# HeartSound_LungSound.net
KiCad netlist of a schematic drawn in Altium Designer
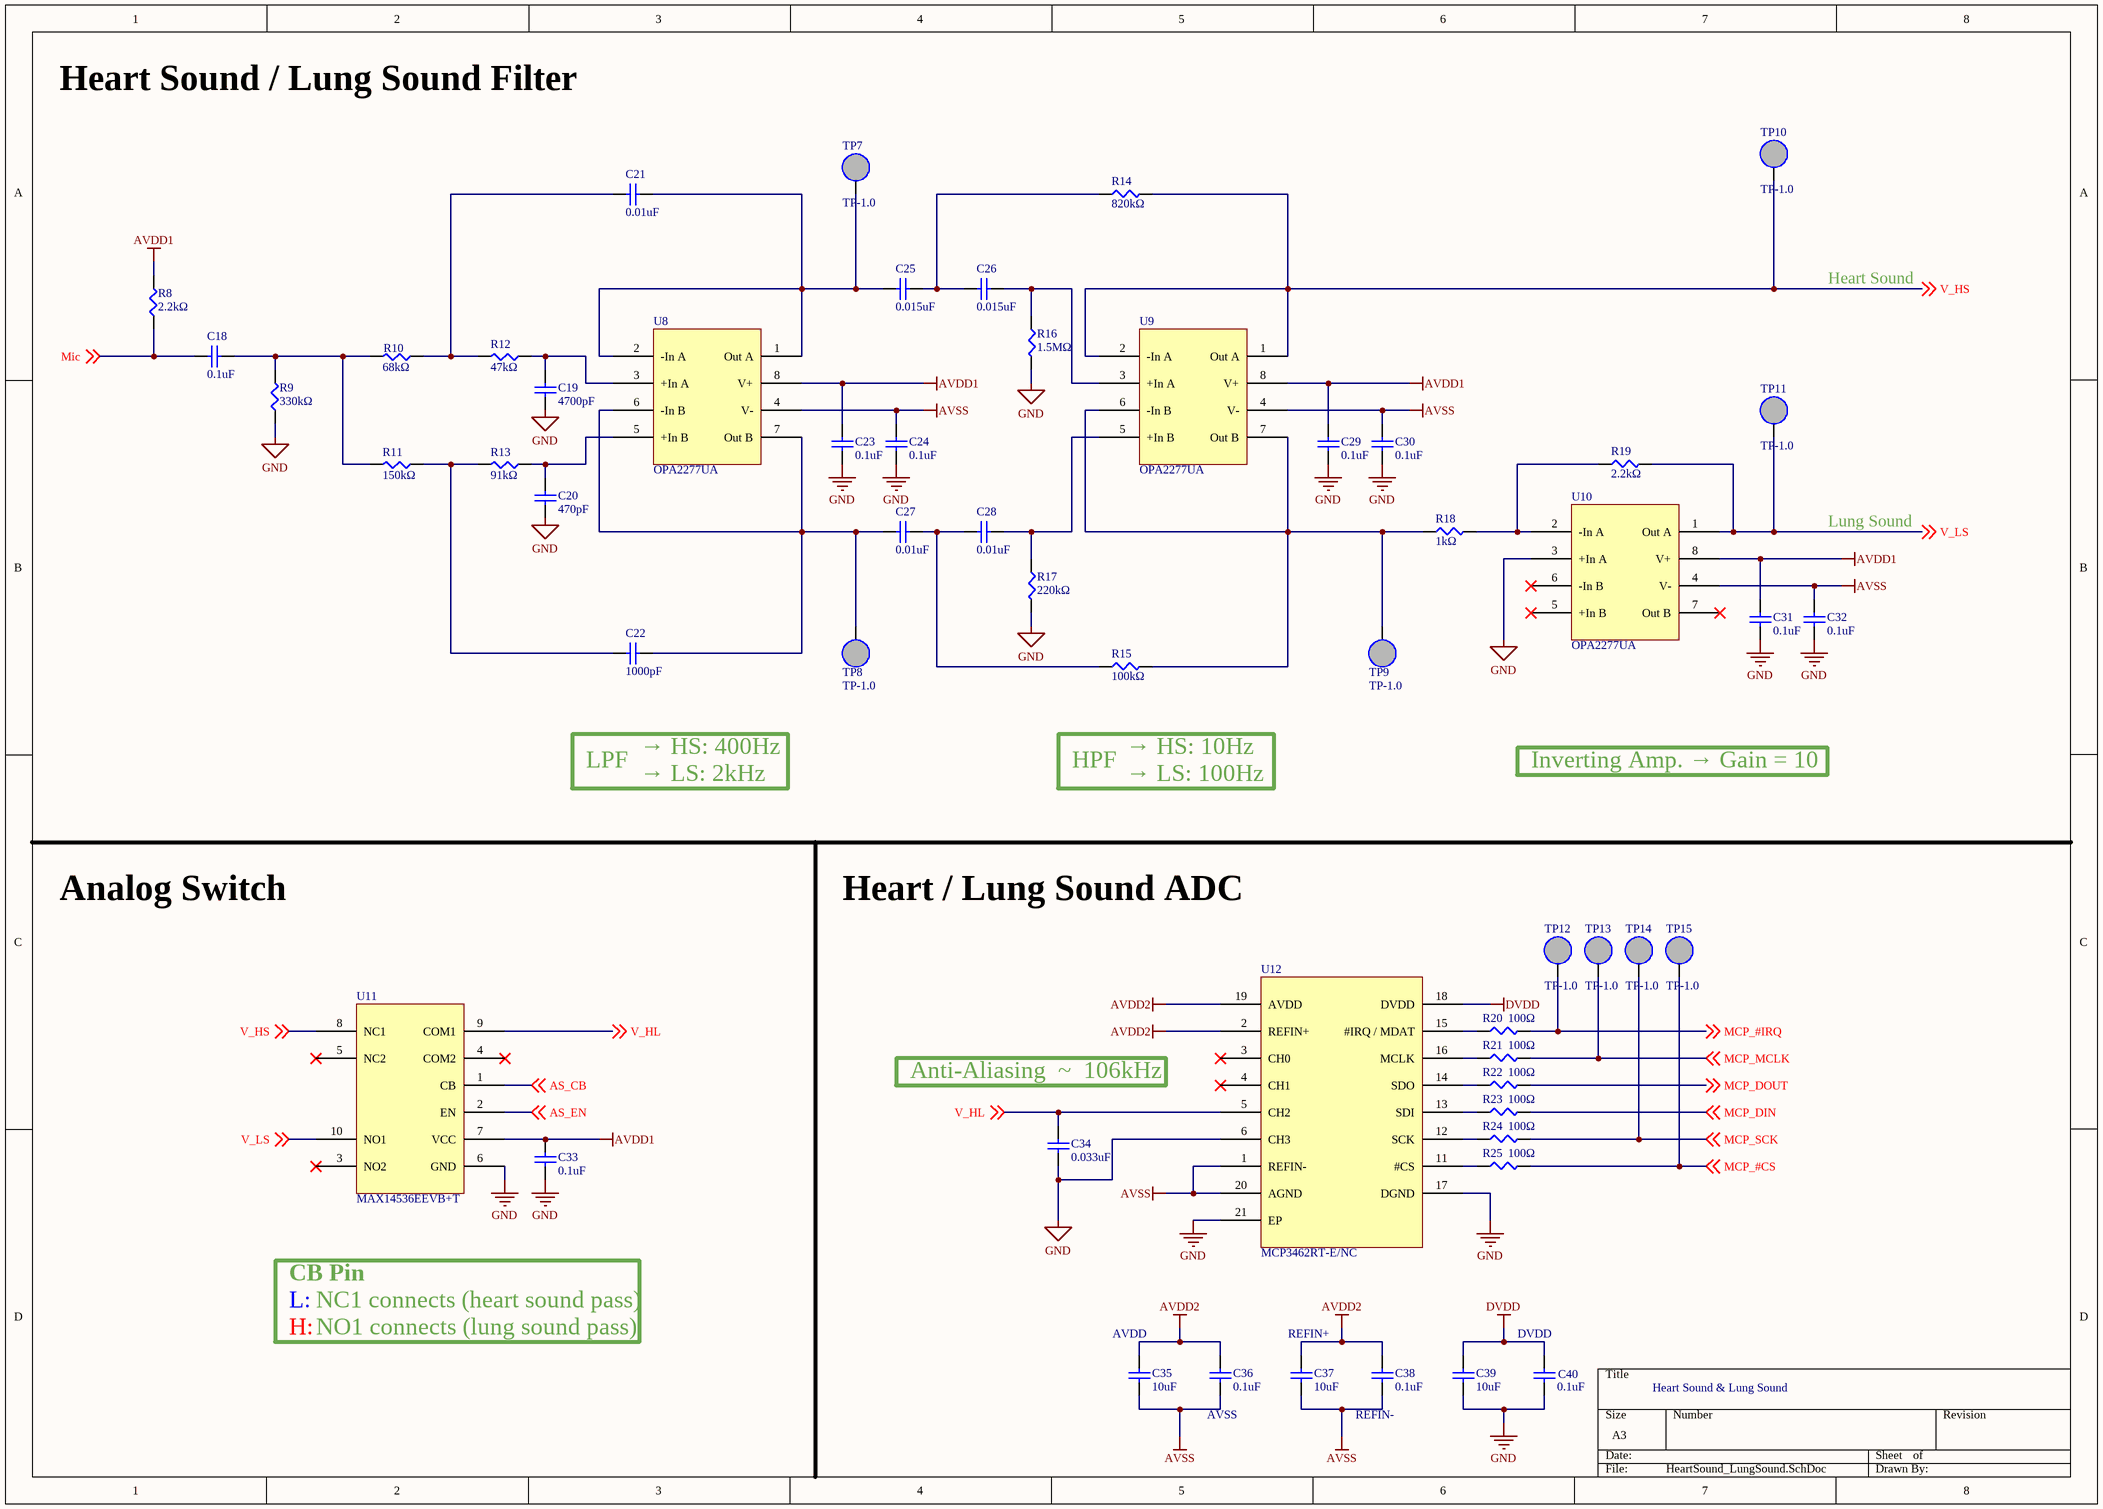
[diagram p0: HeartSound_LungSound.SchDoc]

(export (version "E")
  (design (tool "Eeschema 10.0.6"))
  (components
    (comp (ref "C18")
      (value "0.1uF")
      (footprint "0402")
      (description "MLCC-0402")
      (libsource (lib "MLCC") (part "0402"))
    )
    (comp (ref "C19")
      (value "4700pF")
      (footprint "0402")
      (description "MLCC-0402")
      (libsource (lib "MLCC") (part "0402"))
    )
    (comp (ref "C20")
      (value "470pF")
      (footprint "0402")
      (description "MLCC-0402")
      (libsource (lib "MLCC") (part "0402"))
    )
    (comp (ref "C21")
      (value "0.01uF")
      (footprint "0402")
      (description "MLCC-0402")
      (libsource (lib "MLCC") (part "0402"))
    )
    (comp (ref "C22")
      (value "1000pF")
      (footprint "0402")
      (description "MLCC-0402")
      (libsource (lib "MLCC") (part "0402"))
    )
    (comp (ref "C23")
      (value "0.1uF")
      (footprint "0402")
      (description "MLCC-0402")
      (libsource (lib "MLCC") (part "0402"))
    )
    (comp (ref "C24")
      (value "0.1uF")
      (footprint "0402")
      (description "MLCC-0402")
      (libsource (lib "MLCC") (part "0402"))
    )
    (comp (ref "C25")
      (value "0.015uF")
      (footprint "0402")
      (description "MLCC-0402")
      (libsource (lib "MLCC") (part "0402"))
    )
    (comp (ref "C26")
      (value "0.015uF")
      (footprint "0402")
      (description "MLCC-0402")
      (libsource (lib "MLCC") (part "0402"))
    )
    (comp (ref "C27")
      (value "0.01uF")
      (footprint "0402")
      (description "MLCC-0402")
      (libsource (lib "MLCC") (part "0402"))
    )
    (comp (ref "C28")
      (value "0.01uF")
      (footprint "0402")
      (description "MLCC-0402")
      (libsource (lib "MLCC") (part "0402"))
    )
    (comp (ref "C29")
      (value "0.1uF")
      (footprint "0402")
      (description "MLCC-0402")
      (libsource (lib "MLCC") (part "0402"))
    )
    (comp (ref "C30")
      (value "0.1uF")
      (footprint "0402")
      (description "MLCC-0402")
      (libsource (lib "MLCC") (part "0402"))
    )
    (comp (ref "C31")
      (value "0.1uF")
      (footprint "0402")
      (description "MLCC-0402")
      (libsource (lib "MLCC") (part "0402"))
    )
    (comp (ref "C32")
      (value "0.1uF")
      (footprint "0402")
      (description "MLCC-0402")
      (libsource (lib "MLCC") (part "0402"))
    )
    (comp (ref "C33")
      (value "0.1uF")
      (footprint "0402")
      (description "MLCC-0402")
      (libsource (lib "MLCC") (part "0402"))
    )
    (comp (ref "C34")
      (value "0.033uF")
      (footprint "0402")
      (description "MLCC-0402")
      (libsource (lib "MLCC") (part "0402"))
    )
    (comp (ref "C35")
      (value "10uF")
      (footprint "0603")
      (description "MLCC-0603")
      (libsource (lib "MLCC") (part "0603"))
    )
    (comp (ref "C36")
      (value "0.1uF")
      (footprint "0402")
      (description "MLCC-0402")
      (libsource (lib "MLCC") (part "0402"))
    )
    (comp (ref "C37")
      (value "10uF")
      (footprint "0603")
      (description "MLCC-0603")
      (libsource (lib "MLCC") (part "0603"))
    )
    (comp (ref "C38")
      (value "0.1uF")
      (footprint "0402")
      (description "MLCC-0402")
      (libsource (lib "MLCC") (part "0402"))
    )
    (comp (ref "C39")
      (value "10uF")
      (footprint "0603")
      (description "MLCC-0603")
      (libsource (lib "MLCC") (part "0603"))
    )
    (comp (ref "C40")
      (value "0.1uF")
      (footprint "0402")
      (description "MLCC-0402")
      (libsource (lib "MLCC") (part "0402"))
    )
    (comp (ref "R8")
      (value "2.2kΩ")
      (footprint "0402")
      (description "Resistor_SMD_0402")
      (fields (field (name "AUTHORBY") "yjlab"))
      (libsource (lib "Resistor") (part "0402"))
    )
    (comp (ref "R9")
      (value "330kΩ")
      (footprint "0402")
      (description "Resistor_SMD_0402")
      (fields (field (name "AUTHORBY") "yjlab"))
      (libsource (lib "Resistor") (part "0402"))
    )
    (comp (ref "R10")
      (value "68kΩ")
      (footprint "0402")
      (description "Resistor_SMD_0402")
      (fields (field (name "AUTHORBY") "yjlab"))
      (libsource (lib "Resistor") (part "0402"))
    )
    (comp (ref "R11")
      (value "150kΩ")
      (footprint "0402")
      (description "Resistor_SMD_0402")
      (fields (field (name "AUTHORBY") "yjlab"))
      (libsource (lib "Resistor") (part "0402"))
    )
    (comp (ref "R12")
      (value "47kΩ")
      (footprint "0402")
      (description "Resistor_SMD_0402")
      (fields (field (name "AUTHORBY") "yjlab"))
      (libsource (lib "Resistor") (part "0402"))
    )
    (comp (ref "R13")
      (value "91kΩ")
      (footprint "0402")
      (description "Resistor_SMD_0402")
      (fields (field (name "AUTHORBY") "yjlab"))
      (libsource (lib "Resistor") (part "0402"))
    )
    (comp (ref "R14")
      (value "820kΩ")
      (footprint "0402")
      (description "Resistor_SMD_0402")
      (fields (field (name "AUTHORBY") "yjlab"))
      (libsource (lib "Resistor") (part "0402"))
    )
    (comp (ref "R15")
      (value "100kΩ")
      (footprint "0402")
      (description "Resistor_SMD_0402")
      (fields (field (name "AUTHORBY") "yjlab"))
      (libsource (lib "Resistor") (part "0402"))
    )
    (comp (ref "R16")
      (value "1.5MΩ")
      (footprint "0402")
      (description "Resistor_SMD_0402")
      (fields (field (name "AUTHORBY") "yjlab"))
      (libsource (lib "Resistor") (part "0402"))
    )
    (comp (ref "R17")
      (value "220kΩ")
      (footprint "0402")
      (description "Resistor_SMD_0402")
      (fields (field (name "AUTHORBY") "yjlab"))
      (libsource (lib "Resistor") (part "0402"))
    )
    (comp (ref "R18")
      (value "1kΩ")
      (footprint "0402")
      (description "Resistor_SMD_0402")
      (fields (field (name "AUTHORBY") "yjlab"))
      (libsource (lib "Resistor") (part "0402"))
    )
    (comp (ref "R19")
      (value "2.2kΩ")
      (footprint "0402")
      (description "Resistor_SMD_0402")
      (fields (field (name "AUTHORBY") "yjlab"))
      (libsource (lib "Resistor") (part "0402"))
    )
    (comp (ref "R20")
      (value "100Ω")
      (footprint "0402")
      (description "Resistor_SMD_0402")
      (fields (field (name "AUTHORBY") "yjlab"))
      (libsource (lib "Resistor") (part "0402"))
    )
    (comp (ref "R21")
      (value "100Ω")
      (footprint "0402")
      (description "Resistor_SMD_0402")
      (fields (field (name "AUTHORBY") "yjlab"))
      (libsource (lib "Resistor") (part "0402"))
    )
    (comp (ref "R22")
      (value "100Ω")
      (footprint "0402")
      (description "Resistor_SMD_0402")
      (fields (field (name "AUTHORBY") "yjlab"))
      (libsource (lib "Resistor") (part "0402"))
    )
    (comp (ref "R23")
      (value "100Ω")
      (footprint "0402")
      (description "Resistor_SMD_0402")
      (fields (field (name "AUTHORBY") "yjlab"))
      (libsource (lib "Resistor") (part "0402"))
    )
    (comp (ref "R24")
      (value "100Ω")
      (footprint "0402")
      (description "Resistor_SMD_0402")
      (fields (field (name "AUTHORBY") "yjlab"))
      (libsource (lib "Resistor") (part "0402"))
    )
    (comp (ref "R25")
      (value "100Ω")
      (footprint "0402")
      (description "Resistor_SMD_0402")
      (fields (field (name "AUTHORBY") "yjlab"))
      (libsource (lib "Resistor") (part "0402"))
    )
    (comp (ref "TP7")
      (value "TP-1.0")
      (footprint "Testpoint")
      (libsource (lib "Testpoint") (part "Testpoint"))
    )
    (comp (ref "TP8")
      (value "TP-1.0")
      (footprint "Testpoint")
      (libsource (lib "Testpoint") (part "Testpoint"))
    )
    (comp (ref "TP9")
      (value "TP-1.0")
      (footprint "Testpoint")
      (libsource (lib "Testpoint") (part "Testpoint"))
    )
    (comp (ref "TP10")
      (value "TP-1.0")
      (footprint "Testpoint")
      (libsource (lib "Testpoint") (part "Testpoint"))
    )
    (comp (ref "TP11")
      (value "TP-1.0")
      (footprint "Testpoint")
      (libsource (lib "Testpoint") (part "Testpoint"))
    )
    (comp (ref "TP12")
      (value "TP-1.0")
      (footprint "Testpoint")
      (libsource (lib "Testpoint") (part "Testpoint"))
    )
    (comp (ref "TP13")
      (value "TP-1.0")
      (footprint "Testpoint")
      (libsource (lib "Testpoint") (part "Testpoint"))
    )
    (comp (ref "TP14")
      (value "TP-1.0")
      (footprint "Testpoint")
      (libsource (lib "Testpoint") (part "Testpoint"))
    )
    (comp (ref "TP15")
      (value "TP-1.0")
      (footprint "Testpoint")
      (libsource (lib "Testpoint") (part "Testpoint"))
    )
    (comp (ref "U8")
      (value "OPA2277UA")
      (footprint "SOIC-8")
      (description "High Precision OP Amp, 2 Channel")
      (libsource (lib "OPAx277") (part "OPA2277UA"))
    )
    (comp (ref "U9")
      (value "OPA2277UA")
      (footprint "SOIC-8")
      (description "High Precision OP Amp, 2 Channel")
      (libsource (lib "OPAx277") (part "OPA2277UA"))
    )
    (comp (ref "U10")
      (value "OPA2277UA")
      (footprint "SOIC-8")
      (description "High Precision OP Amp, 2 Channel")
      (libsource (lib "OPAx277") (part "OPA2277UA"))
    )
    (comp (ref "U11")
      (value "MAX14536EEVB+T")
      (footprint "ULTRA-TQFN-10")
      (description "Analog Switch, 0.135 (Ω) On-Resistence")
      (libsource (lib "MAX14536E") (part "MAX14536EEVB+T"))
    )
    (comp (ref "U12")
      (value "MCP3462RT-E/NC")
      (footprint "UQFN-20")
      (description "Delta-to-Sigma ADC, 16 Bit, 2 Channel")
      (libsource (lib "MCP346x") (part "MCP3462RT-E/NC"))
    )
  )
  (nets
    (net (code "1") (name "AS_CB") (class "Default")
      (node (ref "U11") (pin "1") (pinfunction "CB_1") (pintype "passive"))
    )
    (net (code "2") (name "AS_EN") (class "Default")
      (node (ref "U11") (pin "2") (pinfunction "EN_2") (pintype "passive"))
    )
    (net (code "3") (name "AVDD1") (class "Default")
      (node (ref "C23") (pin "1") (pinfunction "1_1") (pintype "passive"))
      (node (ref "C29") (pin "2") (pinfunction "2_2") (pintype "passive"))
      (node (ref "C31") (pin "2") (pinfunction "2_2") (pintype "passive"))
      (node (ref "C33") (pin "2") (pinfunction "2_2") (pintype "passive"))
      (node (ref "R8") (pin "2") (pinfunction "2_2") (pintype "passive"))
      (node (ref "U10") (pin "8") (pinfunction "V+_8") (pintype "passive"))
      (node (ref "U11") (pin "7") (pinfunction "VCC_7") (pintype "passive"))
      (node (ref "U8") (pin "8") (pinfunction "V+_8") (pintype "passive"))
      (node (ref "U9") (pin "8") (pinfunction "V+_8") (pintype "passive"))
    )
    (net (code "4") (name "AVDD2") (class "Default")
      (node (ref "C35") (pin "2") (pinfunction "2_2") (pintype "passive"))
      (node (ref "C36") (pin "2") (pinfunction "2_2") (pintype "passive"))
      (node (ref "C37") (pin "1") (pinfunction "1_1") (pintype "passive"))
      (node (ref "C38") (pin "2") (pinfunction "2_2") (pintype "passive"))
      (node (ref "U12") (pin "19") (pinfunction "AVDD_19") (pintype "passive"))
      (node (ref "U12") (pin "2") (pinfunction "REFIN+_2") (pintype "passive"))
    )
    (net (code "5") (name "AVSS") (class "Default")
      (node (ref "C24") (pin "2") (pinfunction "2_2") (pintype "passive"))
      (node (ref "C30") (pin "1") (pinfunction "1_1") (pintype "passive"))
      (node (ref "C32") (pin "1") (pinfunction "1_1") (pintype "passive"))
      (node (ref "C35") (pin "1") (pinfunction "1_1") (pintype "passive"))
      (node (ref "C36") (pin "1") (pinfunction "1_1") (pintype "passive"))
      (node (ref "C37") (pin "2") (pinfunction "2_2") (pintype "passive"))
      (node (ref "C38") (pin "1") (pinfunction "1_1") (pintype "passive"))
      (node (ref "U10") (pin "4") (pinfunction "V-_4") (pintype "passive"))
      (node (ref "U12") (pin "1") (pinfunction "REFIN-_1") (pintype "passive"))
      (node (ref "U12") (pin "20") (pinfunction "AGND_20") (pintype "passive"))
      (node (ref "U8") (pin "4") (pinfunction "V-_4") (pintype "passive"))
      (node (ref "U9") (pin "4") (pinfunction "V-_4") (pintype "passive"))
    )
    (net (code "6") (name "DVDD") (class "Default")
      (node (ref "C39") (pin "2") (pinfunction "2_2") (pintype "passive"))
      (node (ref "C40") (pin "2") (pinfunction "2_2") (pintype "passive"))
      (node (ref "U12") (pin "18") (pinfunction "DVDD_18") (pintype "passive"))
    )
    (net (code "7") (name "GND") (class "Default")
      (node (ref "C19") (pin "2") (pinfunction "2_2") (pintype "passive"))
      (node (ref "C20") (pin "2") (pinfunction "2_2") (pintype "passive"))
      (node (ref "C23") (pin "2") (pinfunction "2_2") (pintype "passive"))
      (node (ref "C24") (pin "1") (pinfunction "1_1") (pintype "passive"))
      (node (ref "C29") (pin "1") (pinfunction "1_1") (pintype "passive"))
      (node (ref "C30") (pin "2") (pinfunction "2_2") (pintype "passive"))
      (node (ref "C31") (pin "1") (pinfunction "1_1") (pintype "passive"))
      (node (ref "C32") (pin "2") (pinfunction "2_2") (pintype "passive"))
      (node (ref "C33") (pin "1") (pinfunction "1_1") (pintype "passive"))
      (node (ref "C34") (pin "2") (pinfunction "2_2") (pintype "passive"))
      (node (ref "C39") (pin "1") (pinfunction "1_1") (pintype "passive"))
      (node (ref "C40") (pin "1") (pinfunction "1_1") (pintype "passive"))
      (node (ref "R16") (pin "2") (pinfunction "2_2") (pintype "passive"))
      (node (ref "R17") (pin "2") (pinfunction "2_2") (pintype "passive"))
      (node (ref "R9") (pin "1") (pinfunction "1_1") (pintype "passive"))
      (node (ref "U10") (pin "3") (pinfunction "+In_A_3") (pintype "passive"))
      (node (ref "U11") (pin "6") (pinfunction "GND_6") (pintype "passive"))
      (node (ref "U12") (pin "17") (pinfunction "DGND_17") (pintype "passive"))
      (node (ref "U12") (pin "21") (pinfunction "EP_21") (pintype "passive"))
      (node (ref "U12") (pin "6") (pinfunction "CH3_6") (pintype "passive"))
    )
    (net (code "8") (name "MCP_#CS") (class "Default")
      (node (ref "R25") (pin "2") (pinfunction "2_2") (pintype "passive"))
      (node (ref "TP15") (pin "1") (pinfunction "1_1") (pintype "passive"))
    )
    (net (code "9") (name "MCP_#IRQ") (class "Default")
      (node (ref "R20") (pin "2") (pinfunction "2_2") (pintype "passive"))
      (node (ref "TP12") (pin "1") (pinfunction "1_1") (pintype "passive"))
    )
    (net (code "10") (name "MCP_DIN") (class "Default")
      (node (ref "R23") (pin "2") (pinfunction "2_2") (pintype "passive"))
    )
    (net (code "11") (name "MCP_DOUT") (class "Default")
      (node (ref "R22") (pin "2") (pinfunction "2_2") (pintype "passive"))
    )
    (net (code "12") (name "MCP_MCLK") (class "Default")
      (node (ref "R21") (pin "2") (pinfunction "2_2") (pintype "passive"))
      (node (ref "TP13") (pin "1") (pinfunction "1_1") (pintype "passive"))
    )
    (net (code "13") (name "MCP_SCK") (class "Default")
      (node (ref "R24") (pin "2") (pinfunction "2_2") (pintype "passive"))
      (node (ref "TP14") (pin "1") (pinfunction "1_1") (pintype "passive"))
    )
    (net (code "14") (name "Mic") (class "Default")
      (node (ref "C18") (pin "1") (pinfunction "1_1") (pintype "passive"))
      (node (ref "R8") (pin "1") (pinfunction "1_1") (pintype "passive"))
    )
    (net (code "15") (name "Net-(C18-Pad2)") (class "Default")
      (node (ref "C18") (pin "2") (pinfunction "2_2") (pintype "passive"))
      (node (ref "R10") (pin "2") (pinfunction "2_2") (pintype "passive"))
      (node (ref "R11") (pin "2") (pinfunction "2_2") (pintype "passive"))
      (node (ref "R9") (pin "2") (pinfunction "2_2") (pintype "passive"))
    )
    (net (code "16") (name "Net-(C21-Pad2)") (class "Default")
      (node (ref "C21") (pin "2") (pinfunction "2_2") (pintype "passive"))
      (node (ref "R10") (pin "1") (pinfunction "1_1") (pintype "passive"))
      (node (ref "R12") (pin "2") (pinfunction "2_2") (pintype "passive"))
    )
    (net (code "17") (name "Net-(C22-Pad1)") (class "Default")
      (node (ref "C22") (pin "1") (pinfunction "1_1") (pintype "passive"))
      (node (ref "R11") (pin "1") (pinfunction "1_1") (pintype "passive"))
      (node (ref "R13") (pin "2") (pinfunction "2_2") (pintype "passive"))
    )
    (net (code "18") (name "Net-(C25-Pad1)") (class "Default")
      (node (ref "C25") (pin "1") (pinfunction "1_1") (pintype "passive"))
      (node (ref "C26") (pin "2") (pinfunction "2_2") (pintype "passive"))
      (node (ref "R14") (pin "1") (pinfunction "1_1") (pintype "passive"))
    )
    (net (code "19") (name "Net-(C27-Pad1)") (class "Default")
      (node (ref "C27") (pin "1") (pinfunction "1_1") (pintype "passive"))
      (node (ref "C28") (pin "2") (pinfunction "2_2") (pintype "passive"))
      (node (ref "R15") (pin "1") (pinfunction "1_1") (pintype "passive"))
    )
    (net (code "20") (name "Net-(U8-+In_A)") (class "Default")
      (node (ref "C19") (pin "1") (pinfunction "1_1") (pintype "passive"))
      (node (ref "R12") (pin "1") (pinfunction "1_1") (pintype "passive"))
      (node (ref "U8") (pin "3") (pinfunction "+In_A_3") (pintype "passive"))
    )
    (net (code "21") (name "Net-(U8-+In_B)") (class "Default")
      (node (ref "C20") (pin "1") (pinfunction "1_1") (pintype "passive"))
      (node (ref "R13") (pin "1") (pinfunction "1_1") (pintype "passive"))
      (node (ref "U8") (pin "5") (pinfunction "+In_B_5") (pintype "passive"))
    )
    (net (code "22") (name "Net-(U8--In_A)") (class "Default")
      (node (ref "C21") (pin "1") (pinfunction "1_1") (pintype "passive"))
      (node (ref "C25") (pin "2") (pinfunction "2_2") (pintype "passive"))
      (node (ref "TP7") (pin "1") (pinfunction "1_1") (pintype "passive"))
      (node (ref "U8") (pin "1") (pinfunction "Out_A_1") (pintype "passive"))
      (node (ref "U8") (pin "2") (pinfunction "-In_A_2") (pintype "passive"))
    )
    (net (code "23") (name "Net-(U8--In_B)") (class "Default")
      (node (ref "C22") (pin "2") (pinfunction "2_2") (pintype "passive"))
      (node (ref "C27") (pin "2") (pinfunction "2_2") (pintype "passive"))
      (node (ref "TP8") (pin "1") (pinfunction "1_1") (pintype "passive"))
      (node (ref "U8") (pin "6") (pinfunction "-In_B_6") (pintype "passive"))
      (node (ref "U8") (pin "7") (pinfunction "Out_B_7") (pintype "passive"))
    )
    (net (code "24") (name "Net-(U9-+In_A)") (class "Default")
      (node (ref "C26") (pin "1") (pinfunction "1_1") (pintype "passive"))
      (node (ref "R16") (pin "1") (pinfunction "1_1") (pintype "passive"))
      (node (ref "U9") (pin "3") (pinfunction "+In_A_3") (pintype "passive"))
    )
    (net (code "25") (name "Net-(U9-+In_B)") (class "Default")
      (node (ref "C28") (pin "1") (pinfunction "1_1") (pintype "passive"))
      (node (ref "R17") (pin "1") (pinfunction "1_1") (pintype "passive"))
      (node (ref "U9") (pin "5") (pinfunction "+In_B_5") (pintype "passive"))
    )
    (net (code "26") (name "Net-(U9--In_B)") (class "Default")
      (node (ref "R15") (pin "2") (pinfunction "2_2") (pintype "passive"))
      (node (ref "R18") (pin "1") (pinfunction "1_1") (pintype "passive"))
      (node (ref "TP9") (pin "1") (pinfunction "1_1") (pintype "passive"))
      (node (ref "U9") (pin "6") (pinfunction "-In_B_6") (pintype "passive"))
      (node (ref "U9") (pin "7") (pinfunction "Out_B_7") (pintype "passive"))
    )
    (net (code "27") (name "Net-(U10--In_A)") (class "Default")
      (node (ref "R18") (pin "2") (pinfunction "2_2") (pintype "passive"))
      (node (ref "R19") (pin "1") (pinfunction "1_1") (pintype "passive"))
      (node (ref "U10") (pin "2") (pinfunction "-In_A_2") (pintype "passive"))
    )
    (net (code "28") (name "Net-(U12-#CS)") (class "Default")
      (node (ref "R25") (pin "1") (pinfunction "1_1") (pintype "passive"))
      (node (ref "U12") (pin "11") (pinfunction "#CS_11") (pintype "passive"))
    )
    (net (code "29") (name "Net-(U12-#IRQ_{slash}_MDAT)") (class "Default")
      (node (ref "R20") (pin "1") (pinfunction "1_1") (pintype "passive"))
      (node (ref "U12") (pin "15") (pinfunction "#IRQ_/_MDAT_15") (pintype "passive"))
    )
    (net (code "30") (name "Net-(U12-MCLK)") (class "Default")
      (node (ref "R21") (pin "1") (pinfunction "1_1") (pintype "passive"))
      (node (ref "U12") (pin "16") (pinfunction "MCLK_16") (pintype "passive"))
    )
    (net (code "31") (name "Net-(U12-SCK)") (class "Default")
      (node (ref "R24") (pin "1") (pinfunction "1_1") (pintype "passive"))
      (node (ref "U12") (pin "12") (pinfunction "SCK_12") (pintype "passive"))
    )
    (net (code "32") (name "Net-(U12-SDI)") (class "Default")
      (node (ref "R23") (pin "1") (pinfunction "1_1") (pintype "passive"))
      (node (ref "U12") (pin "13") (pinfunction "SDI_13") (pintype "passive"))
    )
    (net (code "33") (name "Net-(U12-SDO)") (class "Default")
      (node (ref "R22") (pin "1") (pinfunction "1_1") (pintype "passive"))
      (node (ref "U12") (pin "14") (pinfunction "SDO_14") (pintype "passive"))
    )
    (net (code "34") (name "V_HL") (class "Default")
      (node (ref "C34") (pin "1") (pinfunction "1_1") (pintype "passive"))
      (node (ref "U11") (pin "9") (pinfunction "COM1_9") (pintype "passive"))
      (node (ref "U12") (pin "5") (pinfunction "CH2_5") (pintype "passive"))
    )
    (net (code "35") (name "V_HS") (class "Default")
      (node (ref "R14") (pin "2") (pinfunction "2_2") (pintype "passive"))
      (node (ref "TP10") (pin "1") (pinfunction "1_1") (pintype "passive"))
      (node (ref "U11") (pin "8") (pinfunction "NC1_8") (pintype "passive"))
      (node (ref "U9") (pin "1") (pinfunction "Out_A_1") (pintype "passive"))
      (node (ref "U9") (pin "2") (pinfunction "-In_A_2") (pintype "passive"))
    )
    (net (code "36") (name "V_LS") (class "Default")
      (node (ref "R19") (pin "2") (pinfunction "2_2") (pintype "passive"))
      (node (ref "TP11") (pin "1") (pinfunction "1_1") (pintype "passive"))
      (node (ref "U10") (pin "1") (pinfunction "Out_A_1") (pintype "passive"))
      (node (ref "U11") (pin "10") (pinfunction "NO1_10") (pintype "passive"))
    )
    (net (code "37") (name "unconnected-(U10-+In_B-Pad5)") (class "Default")
      (node (ref "U10") (pin "5") (pinfunction "+In_B_5") (pintype "passive+no_connect"))
    )
    (net (code "38") (name "unconnected-(U10--In_B-Pad6)") (class "Default")
      (node (ref "U10") (pin "6") (pinfunction "-In_B_6") (pintype "passive+no_connect"))
    )
    (net (code "39") (name "unconnected-(U10-Out_B-Pad7)") (class "Default")
      (node (ref "U10") (pin "7") (pinfunction "Out_B_7") (pintype "passive+no_connect"))
    )
    (net (code "40") (name "unconnected-(U11-COM2-Pad4)") (class "Default")
      (node (ref "U11") (pin "4") (pinfunction "COM2_4") (pintype "passive+no_connect"))
    )
    (net (code "41") (name "unconnected-(U11-NC2-Pad5)") (class "Default")
      (node (ref "U11") (pin "5") (pinfunction "NC2_5") (pintype "passive+no_connect"))
    )
    (net (code "42") (name "unconnected-(U11-NO2-Pad3)") (class "Default")
      (node (ref "U11") (pin "3") (pinfunction "NO2_3") (pintype "passive+no_connect"))
    )
    (net (code "43") (name "unconnected-(U12-CH0-Pad3)") (class "Default")
      (node (ref "U12") (pin "3") (pinfunction "CH0_3") (pintype "passive+no_connect"))
    )
    (net (code "44") (name "unconnected-(U12-CH1-Pad4)") (class "Default")
      (node (ref "U12") (pin "4") (pinfunction "CH1_4") (pintype "passive+no_connect"))
    )
  )
)
